# dpMaster.net
KiCad netlist of a schematic drawn in EAGLE
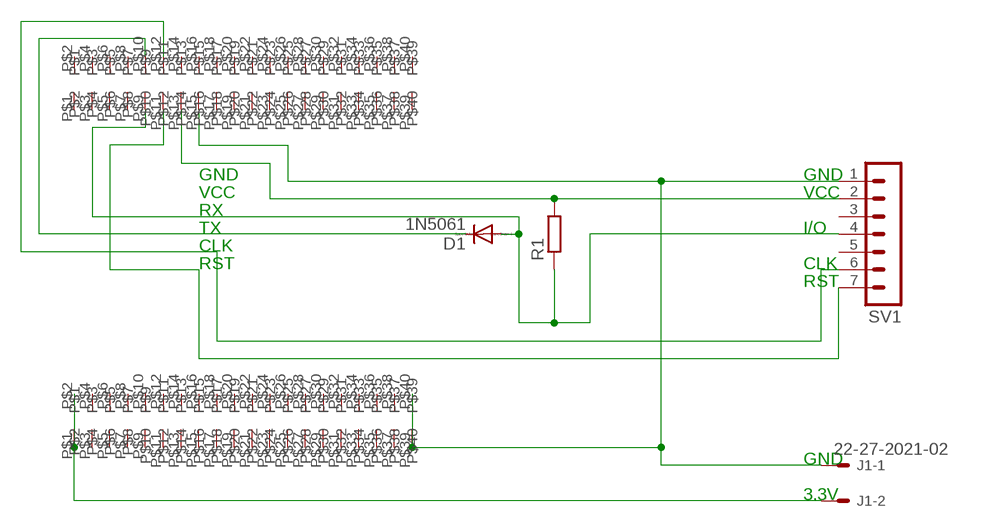
[diagram p0: schematic, sheet 1]

(export (version "E")
  (design (tool "Eeschema 10.0.6"))
  (components
    (comp (ref "D1")
      (value "1N5061")
      (footprint "eagle-import:SOD57-10")
      (libsource (lib "eagle-import") (part "1N5061"))
    )
    (comp (ref "J1")
      (value "22-27-2021-02")
      (footprint "eagle-import:6410-02")
      (libsource (lib "eagle-import") (part "22-?-0227-2021"))
    )
    (comp (ref "R1")
      (value "R-EU_0207/12")
      (footprint "eagle-import:0207_12")
      (libsource (lib "eagle-import") (part "R-EU_0207/12"))
    )
    (comp (ref "SV1")
      (value "MA07-1")
      (footprint "eagle-import:MA07-1")
      (libsource (lib "eagle-import") (part "MA07-1"))
    )
    (comp (ref "U$1")
      (value "SFC-120-T2-L-D")
      (footprint "eagle-import:SFC-120-T2-L-D")
      (libsource (lib "eagle-import") (part "SFC-120-T2-L-D"))
    )
    (comp (ref "U$2")
      (value "SFC-120-T2-L-D")
      (footprint "eagle-import:SFC-120-T2-L-D")
      (libsource (lib "eagle-import") (part "SFC-120-T2-L-D"))
    )
  )
  (nets
    (net (code "1") (name "Net-(D1-PadA)") (class "Default")
      (node (ref "D1") (pin "A") (pinfunction "A_A") (pintype "passive"))
      (node (ref "R1") (pin "1") (pinfunction "1_1") (pintype "passive"))
      (node (ref "SV1") (pin "4") (pinfunction "4_4") (pintype "passive"))
      (node (ref "U$1") (pin "P$9") (pinfunction "P$9_P$9") (pintype "bidirectional"))
    )
    (net (code "2") (name "Net-(D1-PadC)") (class "Default")
      (node (ref "D1") (pin "C") (pinfunction "C_C") (pintype "passive"))
      (node (ref "U$1") (pin "P$10") (pinfunction "P$10_P$10") (pintype "bidirectional"))
    )
    (net (code "3") (name "Net-(J1A-S)") (class "Default")
      (node (ref "J1") (pin "1") (pinfunction "S_1") (pintype "passive"))
      (node (ref "SV1") (pin "1") (pinfunction "1_1") (pintype "passive"))
      (node (ref "U$1") (pin "P$15") (pinfunction "P$15_P$15") (pintype "bidirectional"))
      (node (ref "U$2") (pin "P$39") (pinfunction "P$39_P$39") (pintype "bidirectional"))
      (node (ref "U$2") (pin "P$40") (pinfunction "P$40_P$40") (pintype "bidirectional"))
    )
    (net (code "4") (name "Net-(J1B-S)") (class "Default")
      (node (ref "J1") (pin "2") (pinfunction "S_2") (pintype "passive"))
      (node (ref "U$2") (pin "P$1") (pinfunction "P$1_P$1") (pintype "bidirectional"))
      (node (ref "U$2") (pin "P$2") (pinfunction "P$2_P$2") (pintype "bidirectional"))
    )
    (net (code "5") (name "Net-(R1-Pad2)") (class "Default")
      (node (ref "R1") (pin "2") (pinfunction "2_2") (pintype "passive"))
      (node (ref "SV1") (pin "2") (pinfunction "2_2") (pintype "passive"))
      (node (ref "U$1") (pin "P$13") (pinfunction "P$13_P$13") (pintype "bidirectional"))
    )
    (net (code "6") (name "Net-(SV1-Pad6)") (class "Default")
      (node (ref "SV1") (pin "6") (pinfunction "6_6") (pintype "passive"))
      (node (ref "U$1") (pin "P$12") (pinfunction "P$12_P$12") (pintype "bidirectional"))
    )
    (net (code "7") (name "Net-(SV1-Pad7)") (class "Default")
      (node (ref "SV1") (pin "7") (pinfunction "7_7") (pintype "passive"))
      (node (ref "U$1") (pin "P$11") (pinfunction "P$11_P$11") (pintype "bidirectional"))
    )
    (net (code "8") (name "unconnected-(SV1-Pad3)") (class "Default")
      (node (ref "SV1") (pin "3") (pinfunction "3_3") (pintype "passive"))
    )
    (net (code "9") (name "unconnected-(SV1-Pad5)") (class "Default")
      (node (ref "SV1") (pin "5") (pinfunction "5_5") (pintype "passive"))
    )
    (net (code "10") (name "unconnected-(U$1-PadP$1)") (class "Default")
      (node (ref "U$1") (pin "P$1") (pinfunction "P$1_P$1") (pintype "bidirectional"))
    )
    (net (code "11") (name "unconnected-(U$1-PadP$2)") (class "Default")
      (node (ref "U$1") (pin "P$2") (pinfunction "P$2_P$2") (pintype "bidirectional"))
    )
    (net (code "12") (name "unconnected-(U$1-PadP$3)") (class "Default")
      (node (ref "U$1") (pin "P$3") (pinfunction "P$3_P$3") (pintype "bidirectional"))
    )
    (net (code "13") (name "unconnected-(U$1-PadP$4)") (class "Default")
      (node (ref "U$1") (pin "P$4") (pinfunction "P$4_P$4") (pintype "bidirectional"))
    )
    (net (code "14") (name "unconnected-(U$1-PadP$5)") (class "Default")
      (node (ref "U$1") (pin "P$5") (pinfunction "P$5_P$5") (pintype "bidirectional"))
    )
    (net (code "15") (name "unconnected-(U$1-PadP$6)") (class "Default")
      (node (ref "U$1") (pin "P$6") (pinfunction "P$6_P$6") (pintype "bidirectional"))
    )
    (net (code "16") (name "unconnected-(U$1-PadP$7)") (class "Default")
      (node (ref "U$1") (pin "P$7") (pinfunction "P$7_P$7") (pintype "bidirectional"))
    )
    (net (code "17") (name "unconnected-(U$1-PadP$8)") (class "Default")
      (node (ref "U$1") (pin "P$8") (pinfunction "P$8_P$8") (pintype "bidirectional"))
    )
    (net (code "18") (name "unconnected-(U$1-PadP$14)") (class "Default")
      (node (ref "U$1") (pin "P$14") (pinfunction "P$14_P$14") (pintype "bidirectional"))
    )
    (net (code "19") (name "unconnected-(U$1-PadP$16)") (class "Default")
      (node (ref "U$1") (pin "P$16") (pinfunction "P$16_P$16") (pintype "bidirectional"))
    )
    (net (code "20") (name "unconnected-(U$1-PadP$17)") (class "Default")
      (node (ref "U$1") (pin "P$17") (pinfunction "P$17_P$17") (pintype "bidirectional"))
    )
    (net (code "21") (name "unconnected-(U$1-PadP$18)") (class "Default")
      (node (ref "U$1") (pin "P$18") (pinfunction "P$18_P$18") (pintype "bidirectional"))
    )
    (net (code "22") (name "unconnected-(U$1-PadP$19)") (class "Default")
      (node (ref "U$1") (pin "P$19") (pinfunction "P$19_P$19") (pintype "bidirectional"))
    )
    (net (code "23") (name "unconnected-(U$1-PadP$20)") (class "Default")
      (node (ref "U$1") (pin "P$20") (pinfunction "P$20_P$20") (pintype "bidirectional"))
    )
    (net (code "24") (name "unconnected-(U$1-PadP$21)") (class "Default")
      (node (ref "U$1") (pin "P$21") (pinfunction "P$21_P$21") (pintype "bidirectional"))
    )
    (net (code "25") (name "unconnected-(U$1-PadP$22)") (class "Default")
      (node (ref "U$1") (pin "P$22") (pinfunction "P$22_P$22") (pintype "bidirectional"))
    )
    (net (code "26") (name "unconnected-(U$1-PadP$23)") (class "Default")
      (node (ref "U$1") (pin "P$23") (pinfunction "P$23_P$23") (pintype "bidirectional"))
    )
    (net (code "27") (name "unconnected-(U$1-PadP$24)") (class "Default")
      (node (ref "U$1") (pin "P$24") (pinfunction "P$24_P$24") (pintype "bidirectional"))
    )
    (net (code "28") (name "unconnected-(U$1-PadP$25)") (class "Default")
      (node (ref "U$1") (pin "P$25") (pinfunction "P$25_P$25") (pintype "bidirectional"))
    )
    (net (code "29") (name "unconnected-(U$1-PadP$26)") (class "Default")
      (node (ref "U$1") (pin "P$26") (pinfunction "P$26_P$26") (pintype "bidirectional"))
    )
    (net (code "30") (name "unconnected-(U$1-PadP$27)") (class "Default")
      (node (ref "U$1") (pin "P$27") (pinfunction "P$27_P$27") (pintype "bidirectional"))
    )
    (net (code "31") (name "unconnected-(U$1-PadP$28)") (class "Default")
      (node (ref "U$1") (pin "P$28") (pinfunction "P$28_P$28") (pintype "bidirectional"))
    )
    (net (code "32") (name "unconnected-(U$1-PadP$29)") (class "Default")
      (node (ref "U$1") (pin "P$29") (pinfunction "P$29_P$29") (pintype "bidirectional"))
    )
    (net (code "33") (name "unconnected-(U$1-PadP$30)") (class "Default")
      (node (ref "U$1") (pin "P$30") (pinfunction "P$30_P$30") (pintype "bidirectional"))
    )
    (net (code "34") (name "unconnected-(U$1-PadP$31)") (class "Default")
      (node (ref "U$1") (pin "P$31") (pinfunction "P$31_P$31") (pintype "bidirectional"))
    )
    (net (code "35") (name "unconnected-(U$1-PadP$32)") (class "Default")
      (node (ref "U$1") (pin "P$32") (pinfunction "P$32_P$32") (pintype "bidirectional"))
    )
    (net (code "36") (name "unconnected-(U$1-PadP$33)") (class "Default")
      (node (ref "U$1") (pin "P$33") (pinfunction "P$33_P$33") (pintype "bidirectional"))
    )
    (net (code "37") (name "unconnected-(U$1-PadP$34)") (class "Default")
      (node (ref "U$1") (pin "P$34") (pinfunction "P$34_P$34") (pintype "bidirectional"))
    )
    (net (code "38") (name "unconnected-(U$1-PadP$35)") (class "Default")
      (node (ref "U$1") (pin "P$35") (pinfunction "P$35_P$35") (pintype "bidirectional"))
    )
    (net (code "39") (name "unconnected-(U$1-PadP$36)") (class "Default")
      (node (ref "U$1") (pin "P$36") (pinfunction "P$36_P$36") (pintype "bidirectional"))
    )
    (net (code "40") (name "unconnected-(U$1-PadP$37)") (class "Default")
      (node (ref "U$1") (pin "P$37") (pinfunction "P$37_P$37") (pintype "bidirectional"))
    )
    (net (code "41") (name "unconnected-(U$1-PadP$38)") (class "Default")
      (node (ref "U$1") (pin "P$38") (pinfunction "P$38_P$38") (pintype "bidirectional"))
    )
    (net (code "42") (name "unconnected-(U$1-PadP$39)") (class "Default")
      (node (ref "U$1") (pin "P$39") (pinfunction "P$39_P$39") (pintype "bidirectional"))
    )
    (net (code "43") (name "unconnected-(U$1-PadP$40)") (class "Default")
      (node (ref "U$1") (pin "P$40") (pinfunction "P$40_P$40") (pintype "bidirectional"))
    )
    (net (code "44") (name "unconnected-(U$2-PadP$3)") (class "Default")
      (node (ref "U$2") (pin "P$3") (pinfunction "P$3_P$3") (pintype "bidirectional"))
    )
    (net (code "45") (name "unconnected-(U$2-PadP$4)") (class "Default")
      (node (ref "U$2") (pin "P$4") (pinfunction "P$4_P$4") (pintype "bidirectional"))
    )
    (net (code "46") (name "unconnected-(U$2-PadP$5)") (class "Default")
      (node (ref "U$2") (pin "P$5") (pinfunction "P$5_P$5") (pintype "bidirectional"))
    )
    (net (code "47") (name "unconnected-(U$2-PadP$6)") (class "Default")
      (node (ref "U$2") (pin "P$6") (pinfunction "P$6_P$6") (pintype "bidirectional"))
    )
    (net (code "48") (name "unconnected-(U$2-PadP$7)") (class "Default")
      (node (ref "U$2") (pin "P$7") (pinfunction "P$7_P$7") (pintype "bidirectional"))
    )
    (net (code "49") (name "unconnected-(U$2-PadP$8)") (class "Default")
      (node (ref "U$2") (pin "P$8") (pinfunction "P$8_P$8") (pintype "bidirectional"))
    )
    (net (code "50") (name "unconnected-(U$2-PadP$9)") (class "Default")
      (node (ref "U$2") (pin "P$9") (pinfunction "P$9_P$9") (pintype "bidirectional"))
    )
    (net (code "51") (name "unconnected-(U$2-PadP$10)") (class "Default")
      (node (ref "U$2") (pin "P$10") (pinfunction "P$10_P$10") (pintype "bidirectional"))
    )
    (net (code "52") (name "unconnected-(U$2-PadP$11)") (class "Default")
      (node (ref "U$2") (pin "P$11") (pinfunction "P$11_P$11") (pintype "bidirectional"))
    )
    (net (code "53") (name "unconnected-(U$2-PadP$12)") (class "Default")
      (node (ref "U$2") (pin "P$12") (pinfunction "P$12_P$12") (pintype "bidirectional"))
    )
    (net (code "54") (name "unconnected-(U$2-PadP$13)") (class "Default")
      (node (ref "U$2") (pin "P$13") (pinfunction "P$13_P$13") (pintype "bidirectional"))
    )
    (net (code "55") (name "unconnected-(U$2-PadP$14)") (class "Default")
      (node (ref "U$2") (pin "P$14") (pinfunction "P$14_P$14") (pintype "bidirectional"))
    )
    (net (code "56") (name "unconnected-(U$2-PadP$15)") (class "Default")
      (node (ref "U$2") (pin "P$15") (pinfunction "P$15_P$15") (pintype "bidirectional"))
    )
    (net (code "57") (name "unconnected-(U$2-PadP$16)") (class "Default")
      (node (ref "U$2") (pin "P$16") (pinfunction "P$16_P$16") (pintype "bidirectional"))
    )
    (net (code "58") (name "unconnected-(U$2-PadP$17)") (class "Default")
      (node (ref "U$2") (pin "P$17") (pinfunction "P$17_P$17") (pintype "bidirectional"))
    )
    (net (code "59") (name "unconnected-(U$2-PadP$18)") (class "Default")
      (node (ref "U$2") (pin "P$18") (pinfunction "P$18_P$18") (pintype "bidirectional"))
    )
    (net (code "60") (name "unconnected-(U$2-PadP$19)") (class "Default")
      (node (ref "U$2") (pin "P$19") (pinfunction "P$19_P$19") (pintype "bidirectional"))
    )
    (net (code "61") (name "unconnected-(U$2-PadP$20)") (class "Default")
      (node (ref "U$2") (pin "P$20") (pinfunction "P$20_P$20") (pintype "bidirectional"))
    )
    (net (code "62") (name "unconnected-(U$2-PadP$21)") (class "Default")
      (node (ref "U$2") (pin "P$21") (pinfunction "P$21_P$21") (pintype "bidirectional"))
    )
    (net (code "63") (name "unconnected-(U$2-PadP$22)") (class "Default")
      (node (ref "U$2") (pin "P$22") (pinfunction "P$22_P$22") (pintype "bidirectional"))
    )
    (net (code "64") (name "unconnected-(U$2-PadP$23)") (class "Default")
      (node (ref "U$2") (pin "P$23") (pinfunction "P$23_P$23") (pintype "bidirectional"))
    )
    (net (code "65") (name "unconnected-(U$2-PadP$24)") (class "Default")
      (node (ref "U$2") (pin "P$24") (pinfunction "P$24_P$24") (pintype "bidirectional"))
    )
    (net (code "66") (name "unconnected-(U$2-PadP$25)") (class "Default")
      (node (ref "U$2") (pin "P$25") (pinfunction "P$25_P$25") (pintype "bidirectional"))
    )
    (net (code "67") (name "unconnected-(U$2-PadP$26)") (class "Default")
      (node (ref "U$2") (pin "P$26") (pinfunction "P$26_P$26") (pintype "bidirectional"))
    )
    (net (code "68") (name "unconnected-(U$2-PadP$27)") (class "Default")
      (node (ref "U$2") (pin "P$27") (pinfunction "P$27_P$27") (pintype "bidirectional"))
    )
    (net (code "69") (name "unconnected-(U$2-PadP$28)") (class "Default")
      (node (ref "U$2") (pin "P$28") (pinfunction "P$28_P$28") (pintype "bidirectional"))
    )
    (net (code "70") (name "unconnected-(U$2-PadP$29)") (class "Default")
      (node (ref "U$2") (pin "P$29") (pinfunction "P$29_P$29") (pintype "bidirectional"))
    )
    (net (code "71") (name "unconnected-(U$2-PadP$30)") (class "Default")
      (node (ref "U$2") (pin "P$30") (pinfunction "P$30_P$30") (pintype "bidirectional"))
    )
    (net (code "72") (name "unconnected-(U$2-PadP$31)") (class "Default")
      (node (ref "U$2") (pin "P$31") (pinfunction "P$31_P$31") (pintype "bidirectional"))
    )
    (net (code "73") (name "unconnected-(U$2-PadP$32)") (class "Default")
      (node (ref "U$2") (pin "P$32") (pinfunction "P$32_P$32") (pintype "bidirectional"))
    )
    (net (code "74") (name "unconnected-(U$2-PadP$33)") (class "Default")
      (node (ref "U$2") (pin "P$33") (pinfunction "P$33_P$33") (pintype "bidirectional"))
    )
    (net (code "75") (name "unconnected-(U$2-PadP$34)") (class "Default")
      (node (ref "U$2") (pin "P$34") (pinfunction "P$34_P$34") (pintype "bidirectional"))
    )
    (net (code "76") (name "unconnected-(U$2-PadP$35)") (class "Default")
      (node (ref "U$2") (pin "P$35") (pinfunction "P$35_P$35") (pintype "bidirectional"))
    )
    (net (code "77") (name "unconnected-(U$2-PadP$36)") (class "Default")
      (node (ref "U$2") (pin "P$36") (pinfunction "P$36_P$36") (pintype "bidirectional"))
    )
    (net (code "78") (name "unconnected-(U$2-PadP$37)") (class "Default")
      (node (ref "U$2") (pin "P$37") (pinfunction "P$37_P$37") (pintype "bidirectional"))
    )
    (net (code "79") (name "unconnected-(U$2-PadP$38)") (class "Default")
      (node (ref "U$2") (pin "P$38") (pinfunction "P$38_P$38") (pintype "bidirectional"))
    )
  )
)
